# power.net
KiCad netlist of a schematic drawn in Altium Designer
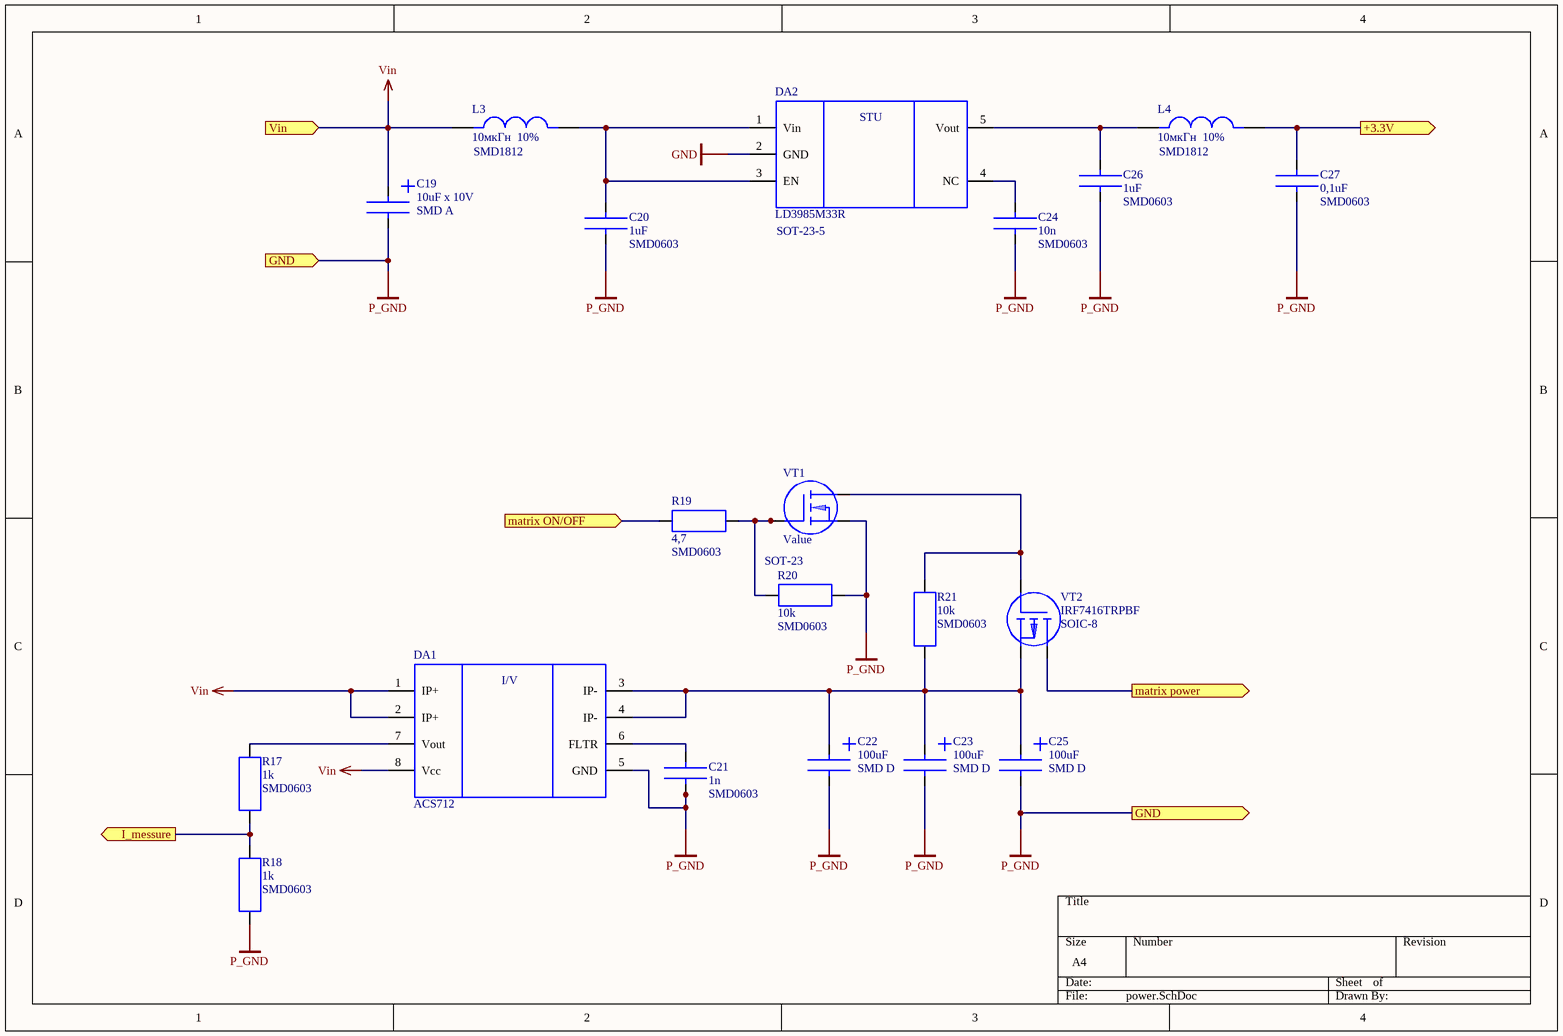
[diagram p0: power.SchDoc]

(export (version "E")
  (design (tool "Eeschema 10.0.6"))
  (components
    (comp (ref "C19")
      (value "10uF x 10V")
      (footprint "TANT_CAP_A(3216)")
      (fields (field (name "PACKAGE") "SMD A"))
      (libsource (lib "MechanikLibrary") (part "C_TANT_A"))
    )
    (comp (ref "C20")
      (value "1uF")
      (footprint "SMD0603(1005)")
      (fields (field (name "PACKAGE") "SMD0603"))
      (libsource (lib "MechanikLibrary") (part "CER_CUP_0603"))
    )
    (comp (ref "C21")
      (value "1n")
      (footprint "SMD0603(1005)")
      (fields (field (name "PACKAGE") "SMD0603"))
      (libsource (lib "MechanikLibrary") (part "CER_CUP_0603"))
    )
    (comp (ref "C22")
      (value "100uF")
      (footprint "TANT_CAP_D(7343)")
      (fields (field (name "PACKAGE") "SMD D"))
      (libsource (lib "MechanikLibrary") (part "C_TANT_D"))
    )
    (comp (ref "C23")
      (value "100uF")
      (footprint "TANT_CAP_D(7343)")
      (fields (field (name "PACKAGE") "SMD D"))
      (libsource (lib "MechanikLibrary") (part "C_TANT_D"))
    )
    (comp (ref "C24")
      (value "10n")
      (footprint "SMD0603(1005)")
      (fields (field (name "PACKAGE") "SMD0603"))
      (libsource (lib "MechanikLibrary") (part "CER_CUP_0603"))
    )
    (comp (ref "C25")
      (value "100uF")
      (footprint "TANT_CAP_D(7343)")
      (fields (field (name "PACKAGE") "SMD D"))
      (libsource (lib "MechanikLibrary") (part "C_TANT_D"))
    )
    (comp (ref "C26")
      (value "1uF")
      (footprint "SMD0603(1005)")
      (fields (field (name "PACKAGE") "SMD0603"))
      (libsource (lib "MechanikLibrary") (part "CER_CUP_0603"))
    )
    (comp (ref "C27")
      (value "0,1uF")
      (footprint "SMD0603(1005)")
      (fields (field (name "PACKAGE") "SMD0603"))
      (libsource (lib "MechanikLibrary") (part "CER_CUP_0603"))
    )
    (comp (ref "DA1")
      (value "ACS712")
      (footprint "SOIC8")
      (libsource (lib "MechanikLibrary") (part "Микросхема ACS712"))
    )
    (comp (ref "DA2")
      (value "LD3985M33R")
      (footprint "SOT23-5")
      (fields (field (name "PACKAGE") "SOT-23-5"))
      (libsource (lib "MechanikLibrary") (part "LD3985M33R"))
    )
    (comp (ref "L3")
      (value "10мкГн  10%")
      (footprint "SMD2010(5025)")
      (fields (field (name "PACKAGE") "SMD1812"))
      (libsource (lib "MechanikLibrary") (part "L1"))
    )
    (comp (ref "L4")
      (value "10мкГн  10%")
      (footprint "SMD2010(5025)")
      (fields (field (name "PACKAGE") "SMD1812"))
      (libsource (lib "MechanikLibrary") (part "L1"))
    )
    (comp (ref "R17")
      (value "1k")
      (footprint "SMD0603(1005)")
      (fields (field (name "PACKAGE") "SMD0603"))
      (libsource (lib "MechanikLibrary") (part "R_0603"))
    )
    (comp (ref "R18")
      (value "1k")
      (footprint "SMD0603(1005)")
      (fields (field (name "PACKAGE") "SMD0603"))
      (libsource (lib "MechanikLibrary") (part "R_0603"))
    )
    (comp (ref "R19")
      (value "4,7")
      (footprint "SMD0603(1005)")
      (fields (field (name "PACKAGE") "SMD0603"))
      (libsource (lib "MechanikLibrary") (part "R_0603"))
    )
    (comp (ref "R20")
      (value "10k")
      (footprint "SMD0603(1005)")
      (fields (field (name "PACKAGE") "SMD0603"))
      (libsource (lib "MechanikLibrary") (part "R_0603"))
    )
    (comp (ref "R21")
      (value "10k")
      (footprint "SMD0603(1005)")
      (fields (field (name "PACKAGE") "SMD0603"))
      (libsource (lib "MechanikLibrary") (part "R_0603"))
    )
    (comp (ref "VT1")
      (value "Value")
      (footprint "SOT23-3")
      (fields (field (name "PACKAGE") "SOT-23"))
      (libsource (lib "MechanikLibrary") (part "VT_N_MOSFET_SOT23_3"))
    )
    (comp (ref "VT2")
      (value "IRF7416TRPBF")
      (footprint "VT_SOIC8")
      (fields (field (name "PACKAGE") "SOIC-8"))
      (libsource (lib "MechanikLibrary") (part "Транзистор IRF7416TRPBF"))
    )
  )
  (nets
    (net (code "1") (name "/+3.3V") (class "Default")
      (node (ref "C27") (pin "1") (pintype "passive"))
      (node (ref "L4") (pin "2") (pinfunction "IN1_2") (pintype "passive"))
    )
    (net (code "2") (name "/I_messure") (class "Default")
      (node (ref "R17") (pin "2") (pintype "passive"))
      (node (ref "R18") (pin "1") (pintype "passive"))
    )
    (net (code "3") (name "/matrix ON{slash}OFF") (class "Default")
      (node (ref "R19") (pin "1") (pintype "passive"))
    )
    (net (code "4") (name "/matrix power") (class "Default") (node (ref "VT2") (pin "3") (pintype "passive")))
    (net (code "5") (name "GND") (class "Default")
      (node (ref "C19") (pin "2") (pintype "passive"))
      (node (ref "C20") (pin "2") (pintype "passive"))
      (node (ref "C21") (pin "2") (pintype "passive"))
      (node (ref "C22") (pin "2") (pintype "passive"))
      (node (ref "C23") (pin "2") (pintype "passive"))
      (node (ref "C24") (pin "2") (pintype "passive"))
      (node (ref "C25") (pin "2") (pintype "passive"))
      (node (ref "C26") (pin "2") (pintype "passive"))
      (node (ref "C27") (pin "2") (pintype "passive"))
      (node (ref "DA1") (pin "5") (pinfunction "GND_5") (pintype "passive"))
      (node (ref "DA2") (pin "2") (pinfunction "GND_2") (pintype "passive"))
      (node (ref "R18") (pin "2") (pintype "passive"))
      (node (ref "R20") (pin "2") (pintype "passive"))
      (node (ref "VT1") (pin "2") (pintype "passive"))
    )
    (net (code "6") (name "Net-(C22-Pad1)") (class "Default")
      (node (ref "C22") (pin "1") (pintype "passive"))
      (node (ref "C23") (pin "1") (pintype "passive"))
      (node (ref "C25") (pin "1") (pintype "passive"))
      (node (ref "DA1") (pin "3") (pinfunction "IP-_3") (pintype "passive"))
      (node (ref "DA1") (pin "4") (pinfunction "IP-_4") (pintype "passive"))
      (node (ref "R21") (pin "2") (pintype "passive"))
      (node (ref "VT2") (pin "1") (pintype "passive"))
    )
    (net (code "7") (name "Net-(DA1-FLTR)") (class "Default")
      (node (ref "C21") (pin "1") (pintype "passive"))
      (node (ref "DA1") (pin "6") (pinfunction "FLTR_6") (pintype "passive"))
    )
    (net (code "8") (name "Net-(DA1-Vout)") (class "Default")
      (node (ref "DA1") (pin "7") (pinfunction "Vout_7") (pintype "passive"))
      (node (ref "R17") (pin "1") (pintype "passive"))
    )
    (net (code "9") (name "Net-(DA2-EN)") (class "Default")
      (node (ref "C20") (pin "1") (pintype "passive"))
      (node (ref "DA2") (pin "1") (pinfunction "Vin_1") (pintype "passive"))
      (node (ref "DA2") (pin "3") (pinfunction "EN_3") (pintype "passive"))
      (node (ref "L3") (pin "2") (pinfunction "IN1_2") (pintype "passive"))
    )
    (net (code "10") (name "Net-(DA2-NC)") (class "Default")
      (node (ref "C24") (pin "1") (pintype "passive"))
      (node (ref "DA2") (pin "4") (pinfunction "NC_4") (pintype "passive"))
    )
    (net (code "11") (name "Net-(DA2-Vout)") (class "Default")
      (node (ref "C26") (pin "1") (pintype "passive"))
      (node (ref "DA2") (pin "5") (pinfunction "Vout_5") (pintype "passive"))
      (node (ref "L4") (pin "1") (pinfunction "IN1_1") (pintype "passive"))
    )
    (net (code "12") (name "Net-(R19-Pad2)") (class "Default")
      (node (ref "R19") (pin "2") (pintype "passive"))
      (node (ref "R20") (pin "1") (pintype "passive"))
      (node (ref "VT1") (pin "1") (pintype "passive"))
    )
    (net (code "13") (name "Net-(R21-Pad1)") (class "Default")
      (node (ref "R21") (pin "1") (pintype "passive"))
      (node (ref "VT1") (pin "3") (pintype "passive"))
      (node (ref "VT2") (pin "2") (pintype "passive"))
    )
    (net (code "14") (name "Vin") (class "Default")
      (node (ref "C19") (pin "1") (pintype "passive"))
      (node (ref "DA1") (pin "1") (pinfunction "IP+_1") (pintype "passive"))
      (node (ref "DA1") (pin "2") (pinfunction "IP+_2") (pintype "passive"))
      (node (ref "DA1") (pin "8") (pinfunction "Vcc_8") (pintype "passive"))
      (node (ref "L3") (pin "1") (pinfunction "IN1_1") (pintype "passive"))
    )
  )
)
